# M8.net
KiCad netlist of a schematic drawn in Altium Designer
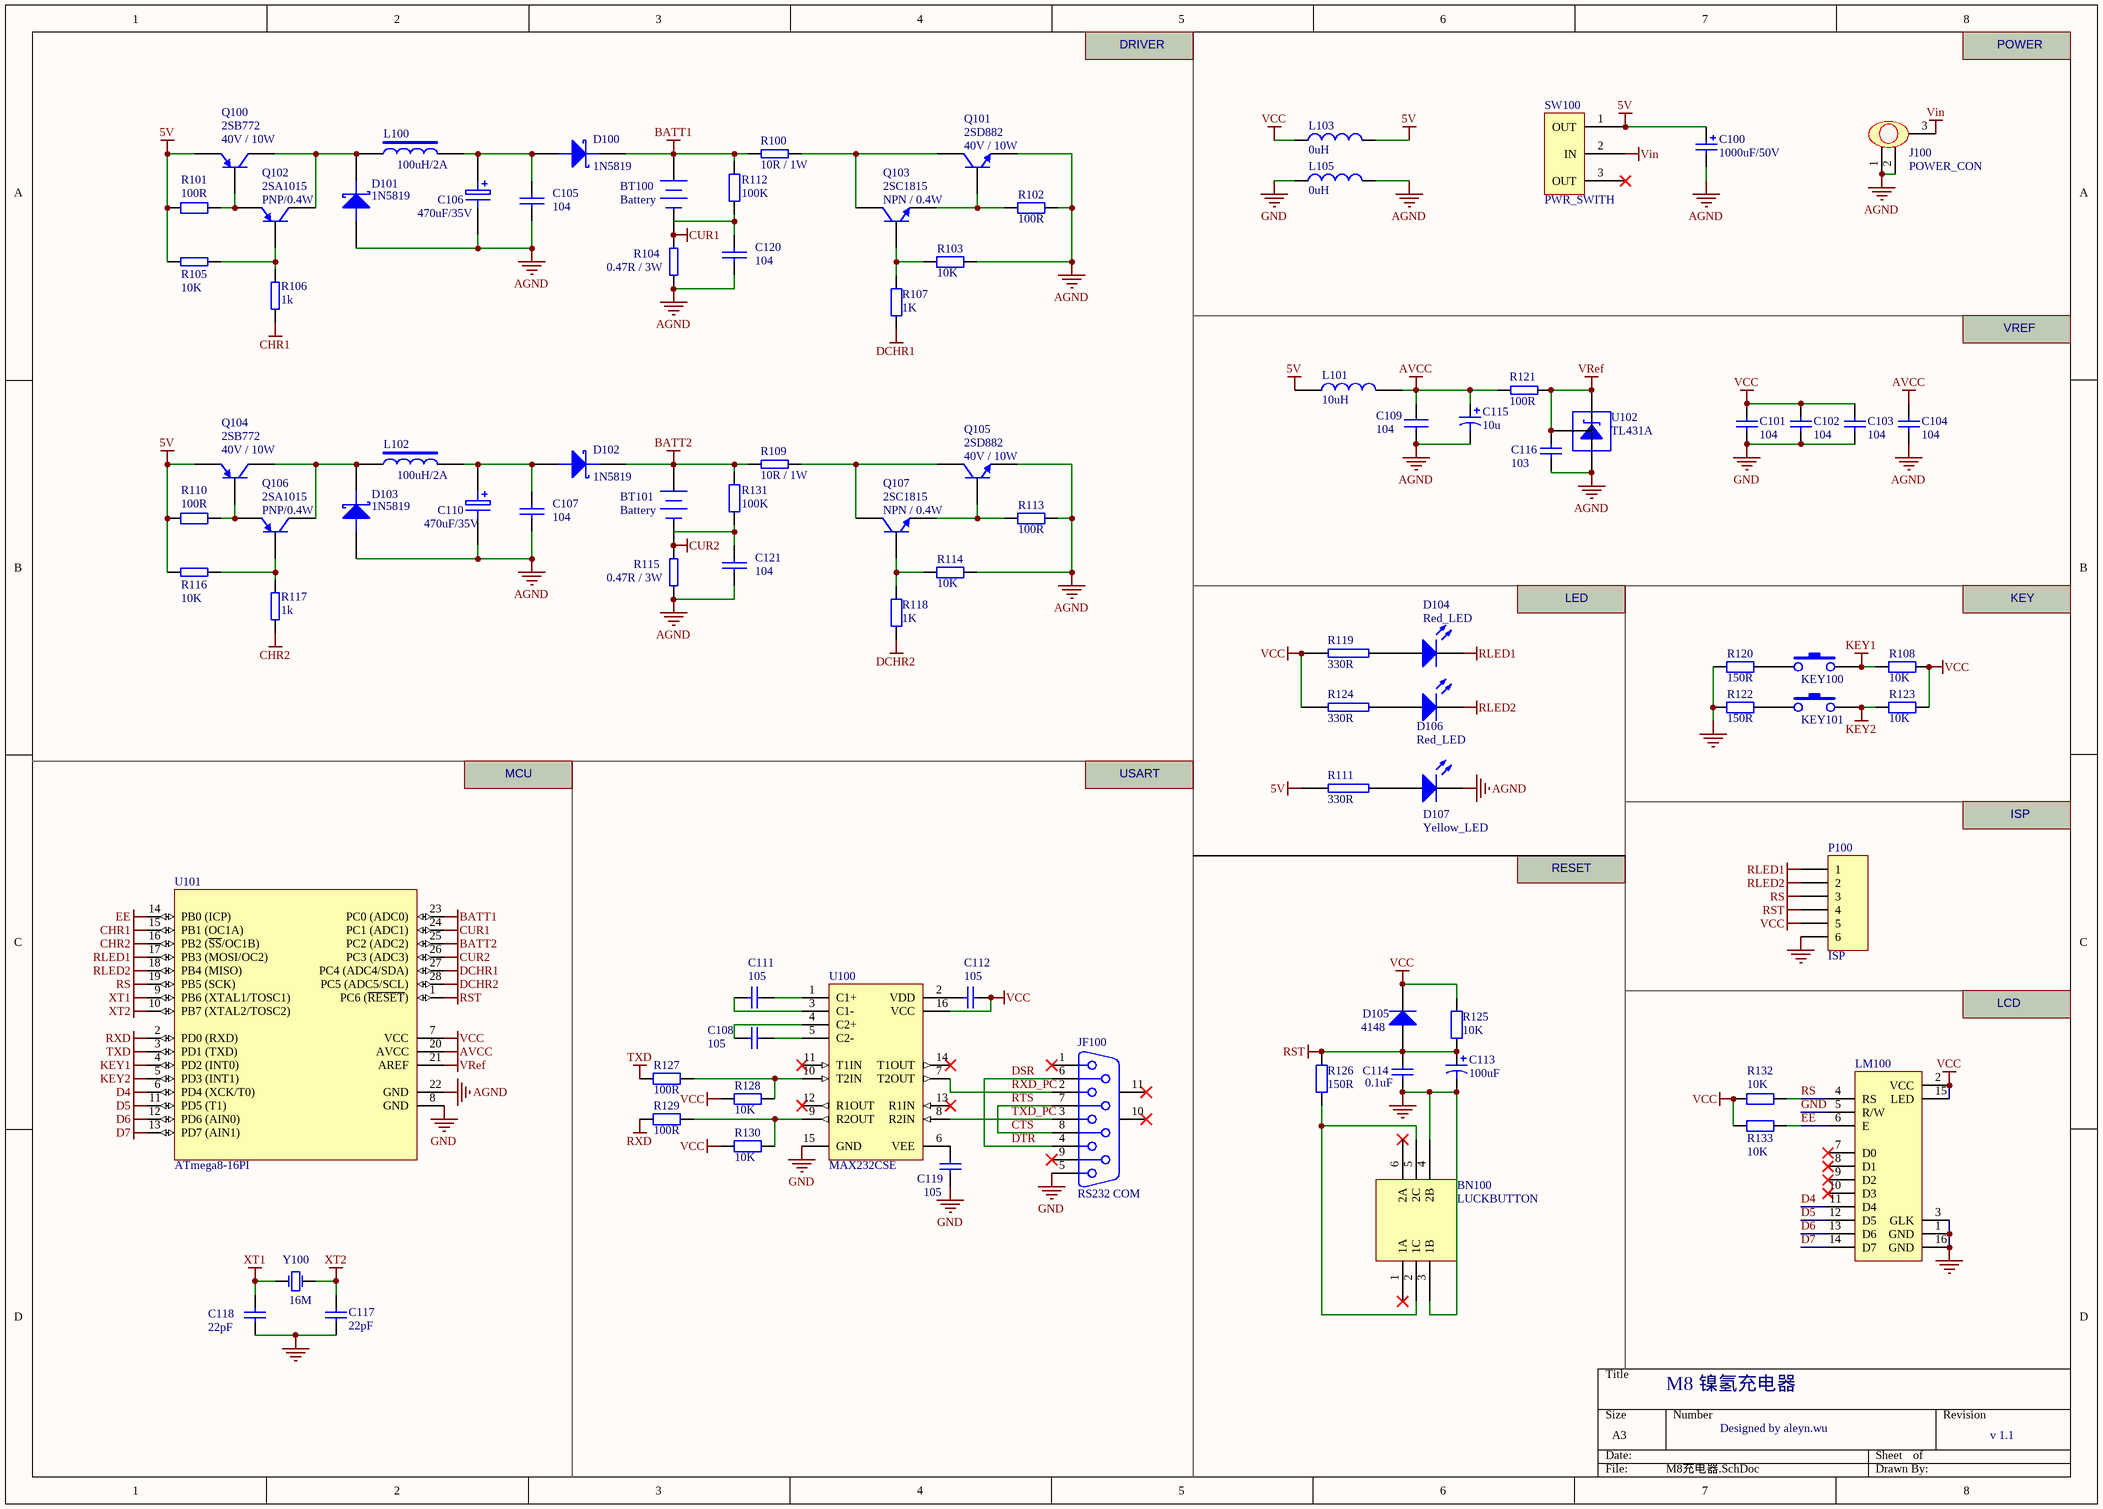
[diagram p0: M8充电器.SchDoc]

(export (version "E")
  (design (tool "Eeschema 10.0.6"))
  (components
    (comp (ref "BN100")
      (value "LUCKBUTTON")
      (footprint "LBTN-01")
      (libsource (lib "AVR_Library") (part "LUCKBUTTON"))
    )
    (comp (ref "BT100")
      (value "Battery")
      (footprint "BAT-2")
      (description "Multicell Battery")
      (fields (field (name "PUBLISHER") "Altium Limited"))
      (libsource (lib "Miscellaneous Devices") (part "Battery"))
    )
    (comp (ref "BT101")
      (value "Battery")
      (footprint "BAT-2")
      (description "Multicell Battery")
      (fields (field (name "PUBLISHER") "Altium Limited"))
      (libsource (lib "Miscellaneous Devices") (part "Battery"))
    )
    (comp (ref "C100")
      (value "1000uF/50V")
      (footprint "C1000uF/50V")
      (description "Polarized Capacitor (Radial)")
      (fields
        (field (name "MANUFACTURER") "Generic Components")
        (field (name "PUBLISHER") "Altium Hobart Technology Centre")
      )
      (libsource (lib "") (part "Cap Pol1_1"))
    )
    (comp (ref "C101")
      (value "104")
      (footprint "0805")
      (description "Capacitor")
      (fields (field (name "PUBLISHER") "Altium Limited"))
      (libsource (lib "Miscellaneous Devices") (part "Cap"))
    )
    (comp (ref "C102")
      (value "104")
      (footprint "0805")
      (description "Capacitor")
      (fields (field (name "PUBLISHER") "Altium Limited"))
      (libsource (lib "Miscellaneous Devices") (part "Cap"))
    )
    (comp (ref "C103")
      (value "104")
      (footprint "0805")
      (description "Capacitor")
      (fields (field (name "PUBLISHER") "Altium Limited"))
      (libsource (lib "Miscellaneous Devices") (part "Cap"))
    )
    (comp (ref "C104")
      (value "104")
      (footprint "0805")
      (description "Capacitor")
      (fields
        (field (name "MANUFACTURER") "Generic Components")
        (field (name "PUBLISHER") "Altium Hobart Technology Centre")
      )
      (libsource (lib "") (part "Cap_1"))
    )
    (comp (ref "C105")
      (value "104")
      (footprint "0805")
      (description "Capacitor")
      (libsource (lib "*") (part "CAP"))
    )
    (comp (ref "C106")
      (value "470uF/35V")
      (footprint "C1000uF/16V")
      (description "Electrolytic Capacitor")
      (libsource (lib "*") (part "ELECTRO1"))
    )
    (comp (ref "C107")
      (value "104")
      (footprint "0805")
      (description "Capacitor")
      (libsource (lib "*") (part "CAP"))
    )
    (comp (ref "C108")
      (value "105")
      (footprint "0805")
      (description "Capacitor")
      (fields
        (field (name "MANUFACTURER") "Generic Components")
        (field (name "PUBLISHER") "Altium Hobart Technology Centre")
      )
      (libsource (lib "Miscellaneous Devices") (part "Cap"))
    )
    (comp (ref "C109") (value "104") (footprint "0805") (libsource (lib "") (part "CAP_1")))
    (comp (ref "C110")
      (value "470uF/35V")
      (footprint "C1000uF/16V")
      (description "Electrolytic Capacitor")
      (libsource (lib "*") (part "ELECTRO1"))
    )
    (comp (ref "C111")
      (value "105")
      (footprint "0805")
      (description "Capacitor")
      (fields
        (field (name "MANUFACTURER") "Generic Components")
        (field (name "PUBLISHER") "Altium Hobart Technology Centre")
      )
      (libsource (lib "Miscellaneous Devices") (part "Cap"))
    )
    (comp (ref "C112")
      (value "105")
      (footprint "0805")
      (description "Capacitor")
      (fields
        (field (name "MANUFACTURER") "Generic Components")
        (field (name "PUBLISHER") "Altium Hobart Technology Centre")
      )
      (libsource (lib "") (part "Cap_1"))
    )
    (comp (ref "C113")
      (value "100uF")
      (footprint "1210")
      (description "Polarized Capacitor (Radial)")
      (fields (field (name "PUBLISHER") "Altium Limited"))
      (libsource (lib "Miscellaneous Devices") (part "Cap Pol1"))
    )
    (comp (ref "C114")
      (value "0.1uF")
      (footprint "0805")
      (description "Capacitor")
      (fields (field (name "PUBLISHER") "Altium Limited"))
      (libsource (lib "Miscellaneous Devices") (part "Cap"))
    )
    (comp (ref "C115")
      (value "10u")
      (footprint "C100UF/10V")
      (description "Polarized Capacitor (Radial)")
      (fields (field (name "PUBLISHER") "Altium Limited"))
      (libsource (lib "Miscellaneous Devices") (part "Cap Pol1"))
    )
    (comp (ref "C116")
      (value "103")
      (footprint "0805")
      (description "Capacitor")
      (fields (field (name "PUBLISHER") "Altium Limited"))
      (libsource (lib "Miscellaneous Devices") (part "Cap"))
    )
    (comp (ref "C117")
      (value "22pF")
      (footprint "0805")
      (description "Capacitor")
      (fields (field (name "PUBLISHER") "Altium Limited"))
      (libsource (lib "Miscellaneous Devices") (part "Cap"))
    )
    (comp (ref "C118")
      (value "22pF")
      (footprint "0805")
      (description "Capacitor")
      (fields (field (name "PUBLISHER") "Altium Limited"))
      (libsource (lib "Miscellaneous Devices") (part "Cap"))
    )
    (comp (ref "C119")
      (value "105")
      (footprint "0805")
      (description "Capacitor")
      (fields
        (field (name "MANUFACTURER") "Generic Components")
        (field (name "PUBLISHER") "Altium Hobart Technology Centre")
      )
      (libsource (lib "Miscellaneous Devices") (part "Cap"))
    )
    (comp (ref "C120")
      (value "104")
      (footprint "0805")
      (description "Capacitor")
      (libsource (lib "*") (part "CAP"))
    )
    (comp (ref "C121")
      (value "104")
      (footprint "0805")
      (description "Capacitor")
      (libsource (lib "*") (part "CAP"))
    )
    (comp (ref "D100")
      (value "1N5819")
      (footprint "IN5822")
      (description "Schottky Diode")
      (libsource (lib "*") (part "DIODE SCHOTTKY"))
    )
    (comp (ref "D101")
      (value "1N5819")
      (footprint "IN5822")
      (description "Schottky Diode")
      (libsource (lib "*") (part "DIODE SCHOTTKY"))
    )
    (comp (ref "D102")
      (value "1N5819")
      (footprint "IN5822")
      (description "Schottky Diode")
      (libsource (lib "*") (part "DIODE SCHOTTKY"))
    )
    (comp (ref "D103")
      (value "1N5819")
      (footprint "IN5822")
      (description "Schottky Diode")
      (libsource (lib "*") (part "DIODE SCHOTTKY"))
    )
    (comp (ref "D104")
      (value "Red_LED")
      (footprint "LED2")
      (description "Typical INFRARED GaAs LED")
      (fields (field (name "PUBLISHER") "Altium Limited"))
      (libsource (lib "Miscellaneous Devices") (part "LED0"))
    )
    (comp (ref "D105")
      (value "4148")
      (footprint "1206D")
      (description "1 Amp General Purpose Rectifier")
      (fields (field (name "PUBLISHER") "Altium Limited"))
      (libsource (lib "Miscellaneous Devices") (part "Diode 1N4001"))
    )
    (comp (ref "D106")
      (value "Red_LED")
      (footprint "LED2")
      (description "Typical INFRARED GaAs LED")
      (fields (field (name "PUBLISHER") "Altium Limited"))
      (libsource (lib "Miscellaneous Devices") (part "LED0"))
    )
    (comp (ref "D107")
      (value "Yellow_LED")
      (footprint "LED2")
      (description "Typical INFRARED GaAs LED")
      (fields (field (name "PUBLISHER") "Altium Limited"))
      (libsource (lib "Miscellaneous Devices") (part "LED0"))
    )
    (comp (ref "J100")
      (value "POWER_CON")
      (footprint "POWER_CON")
      (description "Power Connect")
      (libsource (lib "AVR_Library") (part "POWER_CON"))
    )
    (comp (ref "JF100")
      (value "RS232 COM")
      (footprint "DSUB1.385-2H9")
      (fields
        (field (name "MANUFACTURER") "Generic Components")
        (field (name "PUBLISHER") "Altium Hobart Technology Centre")
      )
      (libsource (lib "AVR_Library") (part "RS232 COM"))
    )
    (comp (ref "KEY100") (value "~") (footprint "BUTTON1") (libsource (lib "*") (part "SW-PB")))
    (comp (ref "KEY101") (value "~") (footprint "BUTTON1") (libsource (lib "*") (part "SW-PB")))
    (comp (ref "L100") (value "100uH/2A") (footprint "INDU20UH") (libsource (lib "*") (part "INDUCTOR2")))
    (comp (ref "L101") (value "10uH") (footprint "1206") (libsource (lib "*") (part "INDUCTOR")))
    (comp (ref "L102") (value "100uH/2A") (footprint "INDU20UH") (libsource (lib "*") (part "INDUCTOR2")))
    (comp (ref "L103")
      (value "0uH")
      (footprint "RES_V1W")
      (description "Inductor")
      (fields
        (field (name "MANUFACTURER") "Generic Components")
        (field (name "PUBLISHER") "Altium Hobart Technology Centre")
      )
      (libsource (lib "Miscellaneous Devices") (part "Inductor"))
    )
    (comp (ref "L105")
      (value "0uH")
      (footprint "RES_V1W")
      (description "Inductor")
      (fields
        (field (name "MANUFACTURER") "Generic Components")
        (field (name "PUBLISHER") "Altium Hobart Technology Centre")
      )
      (libsource (lib "Miscellaneous Devices") (part "Inductor"))
    )
    (comp (ref "LM100")
      (value "TC1602")
      (footprint "HDR2X7")
      (description "LCD TC1602B")
      (libsource (lib "AVR_Library") (part "TC1602B"))
    )
    (comp (ref "P100")
      (value "ISP")
      (footprint "HDR1X6")
      (description "Header, 6-Pin")
      (fields (field (name "PUBLISHER") "Altium Limited"))
      (libsource (lib "Miscellaneous Connectors") (part "Header 6"))
    )
    (comp (ref "Q100")
      (value "2SB772")
      (footprint "TO-262-AA")
      (description "PNP General Purpose Amplifier")
      (fields (field (name "PUBLISHER") "40V / 10W"))
      (libsource (lib "Miscellaneous Devices") (part "2N3906"))
    )
    (comp (ref "Q101")
      (value "2SD882")
      (footprint "TO-262-AA")
      (description "NPN General Purpose Amplifier")
      (fields (field (name "PUBLISHED") "40V / 10W") (field (name "PUBLISHER") "Altium Limited"))
      (libsource (lib "Miscellaneous Devices") (part "2N3904"))
    )
    (comp (ref "Q102")
      (value "2SA1015")
      (footprint "SOT-23/2")
      (description "PNP General Purpose Amplifier")
      (fields (field (name "PUBLISHED") "PNP/0.4W") (field (name "PUBLISHER") "Altium Limited"))
      (libsource (lib "Miscellaneous Devices") (part "2N3906"))
    )
    (comp (ref "Q103")
      (value "2SC1815")
      (footprint "SOT-23/2")
      (description "NPN General Purpose Amplifier")
      (fields (field (name "PUBLISHED") "NPN / 0.4W") (field (name "PUBLISHER") "Altium Limited"))
      (libsource (lib "Miscellaneous Devices") (part "2N3904"))
    )
    (comp (ref "Q104")
      (value "2SB772")
      (footprint "TO-262-AA")
      (description "PNP General Purpose Amplifier")
      (fields (field (name "PUBLISHER") "40V / 10W"))
      (libsource (lib "Miscellaneous Devices") (part "2N3906"))
    )
    (comp (ref "Q105")
      (value "2SD882")
      (footprint "TO-262-AA")
      (description "NPN General Purpose Amplifier")
      (fields (field (name "PUBLISHED") "40V / 10W") (field (name "PUBLISHER") "Altium Limited"))
      (libsource (lib "Miscellaneous Devices") (part "2N3904"))
    )
    (comp (ref "Q106")
      (value "2SA1015")
      (footprint "SOT-23/2")
      (description "PNP General Purpose Amplifier")
      (fields (field (name "PUBLISHED") "PNP/0.4W") (field (name "PUBLISHER") "Altium Limited"))
      (libsource (lib "Miscellaneous Devices") (part "2N3906"))
    )
    (comp (ref "Q107")
      (value "2SC1815")
      (footprint "SOT-23/2")
      (description "NPN General Purpose Amplifier")
      (fields (field (name "PUBLISHED") "NPN / 0.4W") (field (name "PUBLISHER") "Altium Limited"))
      (libsource (lib "Miscellaneous Devices") (part "2N3904"))
    )
    (comp (ref "R100") (value "10R / 1W") (footprint "AXIAL-0.6") (libsource (lib "*") (part "RES5")))
    (comp (ref "R101")
      (value "100R")
      (footprint "AXIAL-0.4")
      (description "Resistor")
      (fields (field (name "PUBLISHER") "Altium Limited"))
      (libsource (lib "") (part "Res2_2"))
    )
    (comp (ref "R102")
      (value "100R")
      (footprint "AXIAL-0.4")
      (description "Resistor")
      (fields (field (name "PUBLISHER") "Altium Limited"))
      (libsource (lib "Miscellaneous Devices") (part "Res2"))
    )
    (comp (ref "R103")
      (value "10K")
      (footprint "0805")
      (description "Resistor")
      (fields (field (name "PUBLISHER") "Altium Limited"))
      (libsource (lib "Miscellaneous Devices") (part "Res2"))
    )
    (comp (ref "R104") (value "0.47R / 3W") (footprint "AXIAL-0.7") (libsource (lib "*") (part "RES5")))
    (comp (ref "R105") (value "10K") (footprint "0805") (libsource (lib "*") (part "RES5")))
    (comp (ref "R106") (value "1k") (footprint "0805") (libsource (lib "*") (part "RES5")))
    (comp (ref "R107")
      (value "1K")
      (footprint "0805")
      (description "Resistor")
      (fields (field (name "PUBLISHER") "Altium Limited"))
      (libsource (lib "") (part "Res2_3"))
    )
    (comp (ref "R108")
      (value "10K")
      (footprint "0805")
      (description "Resistor")
      (fields (field (name "PUBLISHER") "Altium Limited"))
      (libsource (lib "Miscellaneous Devices") (part "Res2"))
    )
    (comp (ref "R109") (value "10R / 1W") (footprint "AXIAL-0.6") (libsource (lib "*") (part "RES5")))
    (comp (ref "R110")
      (value "100R")
      (footprint "AXIAL-0.4")
      (description "Resistor")
      (fields (field (name "PUBLISHER") "Altium Limited"))
      (libsource (lib "") (part "Res2_2"))
    )
    (comp (ref "R111") (value "330R") (footprint "0805") (libsource (lib "*") (part "RES2")))
    (comp (ref "R112")
      (value "100K")
      (footprint "0805")
      (description "Resistor")
      (fields (field (name "PUBLISHER") "Altium Limited"))
      (libsource (lib "") (part "Res2_1"))
    )
    (comp (ref "R113")
      (value "100R")
      (footprint "AXIAL-0.4")
      (description "Resistor")
      (fields (field (name "PUBLISHER") "Altium Limited"))
      (libsource (lib "Miscellaneous Devices") (part "Res2"))
    )
    (comp (ref "R114")
      (value "10K")
      (footprint "0805")
      (description "Resistor")
      (fields (field (name "PUBLISHER") "Altium Limited"))
      (libsource (lib "Miscellaneous Devices") (part "Res2"))
    )
    (comp (ref "R115") (value "0.47R / 3W") (footprint "AXIAL-0.7") (libsource (lib "*") (part "RES5")))
    (comp (ref "R116") (value "10K") (footprint "0805") (libsource (lib "*") (part "RES5")))
    (comp (ref "R117") (value "1k") (footprint "0805") (libsource (lib "*") (part "RES5")))
    (comp (ref "R118")
      (value "1K")
      (footprint "0805")
      (description "Resistor")
      (fields (field (name "PUBLISHER") "Altium Limited"))
      (libsource (lib "") (part "Res2_3"))
    )
    (comp (ref "R119") (value "330R") (footprint "0805") (libsource (lib "*") (part "RES2")))
    (comp (ref "R120")
      (value "150R")
      (footprint "0805")
      (description "Resistor")
      (fields (field (name "PUBLISHER") "Altium Limited"))
      (libsource (lib "Miscellaneous Devices") (part "Res2"))
    )
    (comp (ref "R121") (value "100R") (footprint "0805") (libsource (lib "*") (part "RES5")))
    (comp (ref "R122")
      (value "150R")
      (footprint "0805")
      (description "Resistor")
      (fields (field (name "PUBLISHER") "Altium Limited"))
      (libsource (lib "Miscellaneous Devices") (part "Res2"))
    )
    (comp (ref "R123")
      (value "10K")
      (footprint "0805")
      (description "Resistor")
      (fields (field (name "PUBLISHER") "Altium Limited"))
      (libsource (lib "Miscellaneous Devices") (part "Res2"))
    )
    (comp (ref "R124") (value "330R") (footprint "0805") (libsource (lib "*") (part "RES2")))
    (comp (ref "R125")
      (value "10K")
      (footprint "0805")
      (description "Resistor")
      (fields (field (name "PUBLISHER") "Altium Limited"))
      (libsource (lib "") (part "Res2_1"))
    )
    (comp (ref "R126")
      (value "150R")
      (footprint "0805")
      (description "Resistor")
      (fields (field (name "PUBLISHER") "Altium Limited"))
      (libsource (lib "") (part "Res2_3"))
    )
    (comp (ref "R127")
      (value "100R")
      (footprint "0805")
      (description "Resistor")
      (fields (field (name "PUBLISHER") "Altium Limited"))
      (libsource (lib "") (part "Res2_2"))
    )
    (comp (ref "R128")
      (value "10K")
      (footprint "0805")
      (description "Resistor")
      (fields (field (name "PUBLISHER") "Altium Limited"))
      (libsource (lib "") (part "Res2_3"))
    )
    (comp (ref "R129")
      (value "100R")
      (footprint "0805")
      (description "Resistor")
      (fields (field (name "PUBLISHER") "Altium Limited"))
      (libsource (lib "") (part "Res2_2"))
    )
    (comp (ref "R130")
      (value "10K")
      (footprint "0805")
      (description "Resistor")
      (fields (field (name "PUBLISHER") "Altium Limited"))
      (libsource (lib "") (part "Res2_1"))
    )
    (comp (ref "R131")
      (value "100K")
      (footprint "0805")
      (description "Resistor")
      (fields (field (name "PUBLISHER") "Altium Limited"))
      (libsource (lib "") (part "Res2_1"))
    )
    (comp (ref "R132")
      (value "10K")
      (footprint "0805")
      (description "Resistor")
      (fields (field (name "PUBLISHER") "Altium Limited"))
      (libsource (lib "") (part "Res2_2"))
    )
    (comp (ref "R133")
      (value "10K")
      (footprint "0805")
      (description "Resistor")
      (fields (field (name "PUBLISHER") "Altium Limited"))
      (libsource (lib "") (part "Res2_2"))
    )
    (comp (ref "SW100")
      (value "PWR_SWITH")
      (footprint "POWER_SWITCH2")
      (description "Power Switch")
      (libsource (lib "AVR_Library") (part "PWR_SWITH"))
    )
    (comp (ref "U100")
      (value "MAX232CSE")
      (footprint "SO-16")
      (description "+5V Powered RS-232 Driver/Receiver")
      (fields
        (field (name "MANUFACTURER") "Maxim")
        (field (name "PUBLISHER") "Altium Hobart Technology Centre")
      )
      (libsource (lib "Maxim Communication Transceiver") (part "MAX232CPE"))
    )
    (comp (ref "U101")
      (value "ATmega8-16PI")
      (footprint "32A_N")
      (description "8-Bit AVR Microcontroller with 8K Bytes of In-System Programmable Flash Memory")
      (fields (field (name "PUBLISHER") "Altium Limited"))
      (libsource (lib "Atmel Microcontroller 8-Bit AVR") (part "ATmega8-16PI"))
    )
    (comp (ref "U102") (value "TL431A") (footprint "SOT-89") (libsource (lib "AVR_Library") (part "TL431")))
    (comp (ref "Y100")
      (value "16M")
      (footprint "XTAL")
      (description "Crystal Oscillator")
      (fields
        (field (name "MANUFACTURER") "Generic Components")
        (field (name "PUBLISHER") "Altium Hobart Technology Centre")
      )
      (libsource (lib "AVR_Library") (part "XTAL"))
    )
  )
  (nets
    (net (code "1") (name "/CTS") (class "Default")
      (node (ref "JF100") (pin "7") (pinfunction "7_7") (pintype "passive"))
      (node (ref "JF100") (pin "8") (pinfunction "8_8") (pintype "passive"))
    )
    (net (code "2") (name "/DSR") (class "Default")
      (node (ref "JF100") (pin "4") (pinfunction "4_4") (pintype "passive"))
      (node (ref "JF100") (pin "6") (pinfunction "6_6") (pintype "passive"))
    )
    (net (code "3") (name "/RXD_PC") (class "Default")
      (node (ref "JF100") (pin "2") (pinfunction "2_2") (pintype "passive"))
      (node (ref "U100") (pin "7") (pinfunction "T2OUT_7") (pintype "output"))
    )
    (net (code "4") (name "/TXD_PC") (class "Default")
      (node (ref "JF100") (pin "3") (pinfunction "3_3") (pintype "passive"))
      (node (ref "U100") (pin "8") (pinfunction "R2IN_8") (pintype "input"))
    )
    (net (code "5") (name "5V") (class "Default")
      (node (ref "C100") (pin "1") (pinfunction "1_1") (pintype "passive"))
      (node (ref "L101") (pin "1") (pinfunction "1_1") (pintype "passive"))
      (node (ref "L103") (pin "1") (pinfunction "1_1") (pintype "passive"))
      (node (ref "Q100") (pin "1") (pinfunction "E_1") (pintype "passive"))
      (node (ref "Q104") (pin "1") (pinfunction "E_1") (pintype "passive"))
      (node (ref "R101") (pin "1") (pinfunction "1_1") (pintype "passive"))
      (node (ref "R105") (pin "1") (pinfunction "1_1") (pintype "passive"))
      (node (ref "R110") (pin "1") (pinfunction "1_1") (pintype "passive"))
      (node (ref "R111") (pin "2") (pinfunction "2_2") (pintype "passive"))
      (node (ref "R116") (pin "1") (pinfunction "1_1") (pintype "passive"))
      (node (ref "SW100") (pin "1") (pinfunction "OUT_1") (pintype "passive"))
    )
    (net (code "6") (name "AGND") (class "Default")
      (node (ref "C100") (pin "2") (pinfunction "2_2") (pintype "passive"))
      (node (ref "C104") (pin "2") (pinfunction "2_2") (pintype "passive"))
      (node (ref "C105") (pin "2") (pinfunction "2_2") (pintype "passive"))
      (node (ref "C106") (pin "2") (pinfunction "2_2") (pintype "passive"))
      (node (ref "C107") (pin "2") (pinfunction "2_2") (pintype "passive"))
      (node (ref "C109") (pin "2") (pinfunction "2_2") (pintype "passive"))
      (node (ref "C110") (pin "2") (pinfunction "2_2") (pintype "passive"))
      (node (ref "C115") (pin "2") (pinfunction "2_2") (pintype "passive"))
      (node (ref "C116") (pin "1") (pinfunction "1_1") (pintype "passive"))
      (node (ref "C120") (pin "2") (pinfunction "2_2") (pintype "passive"))
      (node (ref "C121") (pin "2") (pinfunction "2_2") (pintype "passive"))
      (node (ref "D101") (pin "1") (pinfunction "A_1") (pintype "passive"))
      (node (ref "D103") (pin "1") (pinfunction "A_1") (pintype "passive"))
      (node (ref "D107") (pin "2") (pinfunction "K_2") (pintype "passive"))
      (node (ref "J100") (pin "1") (pintype "power_in"))
      (node (ref "J100") (pin "2") (pintype "power_in"))
      (node (ref "L105") (pin "1") (pinfunction "1_1") (pintype "passive"))
      (node (ref "Q101") (pin "1") (pinfunction "E_1") (pintype "passive"))
      (node (ref "Q105") (pin "1") (pinfunction "E_1") (pintype "passive"))
      (node (ref "R102") (pin "1") (pinfunction "1_1") (pintype "passive"))
      (node (ref "R103") (pin "1") (pinfunction "1_1") (pintype "passive"))
      (node (ref "R104") (pin "1") (pinfunction "1_1") (pintype "passive"))
      (node (ref "R113") (pin "1") (pinfunction "1_1") (pintype "passive"))
      (node (ref "R114") (pin "1") (pinfunction "1_1") (pintype "passive"))
      (node (ref "R115") (pin "1") (pinfunction "1_1") (pintype "passive"))
      (node (ref "U101") (pin "22") (pinfunction "GND_22") (pintype "power_in"))
      (node (ref "U102") (pin "2") (pinfunction "2_2") (pintype "power_in"))
    )
    (net (code "7") (name "AVCC") (class "Default")
      (node (ref "C104") (pin "1") (pinfunction "1_1") (pintype "passive"))
      (node (ref "C109") (pin "1") (pinfunction "1_1") (pintype "passive"))
      (node (ref "C115") (pin "1") (pinfunction "1_1") (pintype "passive"))
      (node (ref "L101") (pin "2") (pinfunction "2_2") (pintype "passive"))
      (node (ref "R121") (pin "1") (pinfunction "1_1") (pintype "passive"))
      (node (ref "U101") (pin "20") (pinfunction "AVCC_20") (pintype "power_in"))
    )
    (net (code "8") (name "BATT1") (class "Default")
      (node (ref "BT100") (pin "1") (pinfunction "+_1") (pintype "passive"))
      (node (ref "D100") (pin "2") (pinfunction "K_2") (pintype "passive"))
      (node (ref "R100") (pin "2") (pinfunction "2_2") (pintype "passive"))
      (node (ref "R112") (pin "1") (pinfunction "1_1") (pintype "passive"))
      (node (ref "U101") (pin "23") (pinfunction "PC0_(ADC0)_23") (pintype "bidirectional"))
    )
    (net (code "9") (name "BATT2") (class "Default")
      (node (ref "BT101") (pin "1") (pinfunction "+_1") (pintype "passive"))
      (node (ref "D102") (pin "2") (pinfunction "K_2") (pintype "passive"))
      (node (ref "R109") (pin "2") (pinfunction "2_2") (pintype "passive"))
      (node (ref "R131") (pin "1") (pinfunction "1_1") (pintype "passive"))
      (node (ref "U101") (pin "25") (pinfunction "PC2_(ADC2)_25") (pintype "bidirectional"))
    )
    (net (code "10") (name "CHR1") (class "Default")
      (node (ref "R106") (pin "2") (pinfunction "2_2") (pintype "passive"))
      (node (ref "U101") (pin "15") (pinfunction "PB1_(OC1A)_15") (pintype "bidirectional"))
    )
    (net (code "11") (name "CHR2") (class "Default")
      (node (ref "R117") (pin "2") (pinfunction "2_2") (pintype "passive"))
      (node (ref "U101") (pin "16") (pinfunction "PB2_(~{SS}/OC1B)_16") (pintype "bidirectional"))
    )
    (net (code "12") (name "CUR1") (class "Default")
      (node (ref "BT100") (pin "2") (pinfunction "-_2") (pintype "passive"))
      (node (ref "R104") (pin "2") (pinfunction "2_2") (pintype "passive"))
      (node (ref "U101") (pin "24") (pinfunction "PC1_(ADC1)_24") (pintype "bidirectional"))
    )
    (net (code "13") (name "CUR2") (class "Default")
      (node (ref "BT101") (pin "2") (pinfunction "-_2") (pintype "passive"))
      (node (ref "R115") (pin "2") (pinfunction "2_2") (pintype "passive"))
      (node (ref "U101") (pin "26") (pinfunction "PC3_(ADC3)_26") (pintype "bidirectional"))
    )
    (net (code "14") (name "D4") (class "Default")
      (node (ref "LM100") (pin "11") (pinfunction "D4_11") (pintype "passive"))
      (node (ref "U101") (pin "6") (pinfunction "PD4_(XCK/T0)_6") (pintype "bidirectional"))
    )
    (net (code "15") (name "D5") (class "Default")
      (node (ref "LM100") (pin "12") (pinfunction "D5_12") (pintype "passive"))
      (node (ref "U101") (pin "11") (pinfunction "PD5_(T1)_11") (pintype "bidirectional"))
    )
    (net (code "16") (name "D6") (class "Default")
      (node (ref "LM100") (pin "13") (pinfunction "D6_13") (pintype "passive"))
      (node (ref "U101") (pin "12") (pinfunction "PD6_(AIN0)_12") (pintype "bidirectional"))
    )
    (net (code "17") (name "D7") (class "Default")
      (node (ref "LM100") (pin "14") (pinfunction "D7_14") (pintype "passive"))
      (node (ref "U101") (pin "13") (pinfunction "PD7_(AIN1)_13") (pintype "bidirectional"))
    )
    (net (code "18") (name "DCHR1") (class "Default")
      (node (ref "R107") (pin "1") (pinfunction "1_1") (pintype "passive"))
      (node (ref "U101") (pin "27") (pinfunction "PC4_(ADC4/SDA)_27") (pintype "bidirectional"))
    )
    (net (code "19") (name "DCHR2") (class "Default")
      (node (ref "R118") (pin "1") (pinfunction "1_1") (pintype "passive"))
      (node (ref "U101") (pin "28") (pinfunction "PC5_(ADC5/SCL)_28") (pintype "bidirectional"))
    )
    (net (code "20") (name "EE") (class "Default")
      (node (ref "LM100") (pin "6") (pinfunction "E_6") (pintype "passive"))
      (node (ref "R133") (pin "2") (pinfunction "2_2") (pintype "passive"))
      (node (ref "U101") (pin "14") (pinfunction "PB0_(ICP)_14") (pintype "bidirectional"))
    )
    (net (code "21") (name "GND") (class "Default")
      (node (ref "BN100") (pin "3") (pinfunction "1B_3") (pintype "passive"))
      (node (ref "BN100") (pin "4") (pinfunction "2B_4") (pintype "passive"))
      (node (ref "C101") (pin "1") (pinfunction "1_1") (pintype "passive"))
      (node (ref "C102") (pin "1") (pinfunction "1_1") (pintype "passive"))
      (node (ref "C103") (pin "2") (pinfunction "2_2") (pintype "passive"))
      (node (ref "C113") (pin "2") (pinfunction "2_2") (pintype "passive"))
      (node (ref "C114") (pin "2") (pinfunction "2_2") (pintype "passive"))
      (node (ref "C117") (pin "2") (pinfunction "2_2") (pintype "passive"))
      (node (ref "C118") (pin "2") (pinfunction "2_2") (pintype "passive"))
      (node (ref "C119") (pin "1") (pinfunction "1_1") (pintype "passive"))
      (node (ref "JF100") (pin "5") (pinfunction "5_5") (pintype "passive"))
      (node (ref "L105") (pin "2") (pinfunction "2_2") (pintype "passive"))
      (node (ref "LM100") (pin "1") (pinfunction "GND_1") (pintype "passive"))
      (node (ref "LM100") (pin "16") (pinfunction "GND_16") (pintype "passive"))
      (node (ref "LM100") (pin "3") (pinfunction "GLK_3") (pintype "passive"))
      (node (ref "LM100") (pin "5") (pinfunction "R/W_5") (pintype "passive"))
      (node (ref "P100") (pin "6") (pinfunction "6_6") (pintype "passive"))
      (node (ref "R120") (pin "2") (pinfunction "2_2") (pintype "passive"))
      (node (ref "R122") (pin "2") (pinfunction "2_2") (pintype "passive"))
      (node (ref "U100") (pin "15") (pinfunction "GND_15") (pintype "power_in"))
      (node (ref "U101") (pin "8") (pinfunction "GND_8") (pintype "power_in"))
    )
    (net (code "22") (name "KEY1") (class "Default")
      (node (ref "KEY100") (pin "2") (pinfunction "2_2") (pintype "passive"))
      (node (ref "R108") (pin "2") (pinfunction "2_2") (pintype "passive"))
      (node (ref "U101") (pin "4") (pinfunction "PD2_(INT0)_4") (pintype "bidirectional"))
    )
    (net (code "23") (name "KEY2") (class "Default")
      (node (ref "KEY101") (pin "2") (pinfunction "2_2") (pintype "passive"))
      (node (ref "R123") (pin "2") (pinfunction "2_2") (pintype "passive"))
      (node (ref "U101") (pin "5") (pinfunction "PD3_(INT1)_5") (pintype "bidirectional"))
    )
    (net (code "24") (name "Net-(BN100-1C)") (class "Default")
      (node (ref "BN100") (pin "2") (pinfunction "1C_2") (pintype "passive"))
      (node (ref "BN100") (pin "5") (pinfunction "2C_5") (pintype "passive"))
      (node (ref "R126") (pin "1") (pinfunction "1_1") (pintype "passive"))
    )
    (net (code "25") (name "Net-(C120-Pad1)") (class "Default")
      (node (ref "C120") (pin "1") (pinfunction "1_1") (pintype "passive"))
      (node (ref "R112") (pin "2") (pinfunction "2_2") (pintype "passive"))
    )
    (net (code "26") (name "Net-(C121-Pad1)") (class "Default")
      (node (ref "C121") (pin "1") (pinfunction "1_1") (pintype "passive"))
      (node (ref "R131") (pin "2") (pinfunction "2_2") (pintype "passive"))
    )
    (net (code "27") (name "Net-(D100-A)") (class "Default")
      (node (ref "C105") (pin "1") (pinfunction "1_1") (pintype "passive"))
      (node (ref "C106") (pin "1") (pinfunction "1_1") (pintype "passive"))
      (node (ref "D100") (pin "1") (pinfunction "A_1") (pintype "passive"))
      (node (ref "L100") (pin "2") (pinfunction "2_2") (pintype "passive"))
    )
    (net (code "28") (name "Net-(D101-K)") (class "Default")
      (node (ref "D101") (pin "2") (pinfunction "K_2") (pintype "passive"))
      (node (ref "L100") (pin "1") (pinfunction "1_1") (pintype "passive"))
      (node (ref "Q100") (pin "3") (pinfunction "C_3") (pintype "passive"))
      (node (ref "Q102") (pin "3") (pinfunction "C_3") (pintype "passive"))
    )
    (net (code "29") (name "Net-(D102-A)") (class "Default")
      (node (ref "C107") (pin "1") (pinfunction "1_1") (pintype "passive"))
      (node (ref "C110") (pin "1") (pinfunction "1_1") (pintype "passive"))
      (node (ref "D102") (pin "1") (pinfunction "A_1") (pintype "passive"))
      (node (ref "L102") (pin "2") (pinfunction "2_2") (pintype "passive"))
    )
    (net (code "30") (name "Net-(D103-K)") (class "Default")
      (node (ref "D103") (pin "2") (pinfunction "K_2") (pintype "passive"))
      (node (ref "L102") (pin "1") (pinfunction "1_1") (pintype "passive"))
      (node (ref "Q104") (pin "3") (pinfunction "C_3") (pintype "passive"))
      (node (ref "Q106") (pin "3") (pinfunction "C_3") (pintype "passive"))
    )
    (net (code "31") (name "Net-(D104-A)") (class "Default")
      (node (ref "D104") (pin "1") (pinfunction "A_1") (pintype "passive"))
      (node (ref "R119") (pin "1") (pinfunction "1_1") (pintype "passive"))
    )
    (net (code "32") (name "Net-(D106-A)") (class "Default")
      (node (ref "D106") (pin "1") (pinfunction "A_1") (pintype "passive"))
      (node (ref "R124") (pin "1") (pinfunction "1_1") (pintype "passive"))
    )
    (net (code "33") (name "Net-(D107-A)") (class "Default")
      (node (ref "D107") (pin "1") (pinfunction "A_1") (pintype "passive"))
      (node (ref "R111") (pin "1") (pinfunction "1_1") (pintype "passive"))
    )
    (net (code "34") (name "Net-(KEY100-Pad1)") (class "Default")
      (node (ref "KEY100") (pin "1") (pinfunction "1_1") (pintype "passive"))
      (node (ref "R120") (pin "1") (pinfunction "1_1") (pintype "passive"))
    )
    (net (code "35") (name "Net-(KEY101-Pad1)") (class "Default")
      (node (ref "KEY101") (pin "1") (pinfunction "1_1") (pintype "passive"))
      (node (ref "R122") (pin "1") (pinfunction "1_1") (pintype "passive"))
    )
    (net (code "36") (name "Net-(Q100-B)") (class "Default")
      (node (ref "Q100") (pin "2") (pinfunction "B_2") (pintype "passive"))
      (node (ref "Q102") (pin "1") (pinfunction "E_1") (pintype "passive"))
      (node (ref "R101") (pin "2") (pinfunction "2_2") (pintype "passive"))
    )
    (net (code "37") (name "Net-(Q101-B)") (class "Default")
      (node (ref "Q101") (pin "2") (pinfunction "B_2") (pintype "passive"))
      (node (ref "Q103") (pin "1") (pinfunction "E_1") (pintype "passive"))
      (node (ref "R102") (pin "2") (pinfunction "2_2") (pintype "passive"))
    )
    (net (code "38") (name "Net-(Q101-C)") (class "Default")
      (node (ref "Q101") (pin "3") (pinfunction "C_3") (pintype "passive"))
      (node (ref "Q103") (pin "3") (pinfunction "C_3") (pintype "passive"))
      (node (ref "R100") (pin "1") (pinfunction "1_1") (pintype "passive"))
    )
    (net (code "39") (name "Net-(Q102-B)") (class "Default")
      (node (ref "Q102") (pin "2") (pinfunction "B_2") (pintype "passive"))
      (node (ref "R105") (pin "2") (pinfunction "2_2") (pintype "passive"))
      (node (ref "R106") (pin "1") (pinfunction "1_1") (pintype "passive"))
    )
    (net (code "40") (name "Net-(Q103-B)") (class "Default")
      (node (ref "Q103") (pin "2") (pinfunction "B_2") (pintype "passive"))
      (node (ref "R103") (pin "2") (pinfunction "2_2") (pintype "passive"))
      (node (ref "R107") (pin "2") (pinfunction "2_2") (pintype "passive"))
    )
    (net (code "41") (name "Net-(Q104-B)") (class "Default")
      (node (ref "Q104") (pin "2") (pinfunction "B_2") (pintype "passive"))
      (node (ref "Q106") (pin "1") (pinfunction "E_1") (pintype "passive"))
      (node (ref "R110") (pin "2") (pinfunction "2_2") (pintype "passive"))
    )
    (net (code "42") (name "Net-(Q105-B)") (class "Default")
      (node (ref "Q105") (pin "2") (pinfunction "B_2") (pintype "passive"))
      (node (ref "Q107") (pin "1") (pinfunction "E_1") (pintype "passive"))
      (node (ref "R113") (pin "2") (pinfunction "2_2") (pintype "passive"))
    )
    (net (code "43") (name "Net-(Q105-C)") (class "Default")
      (node (ref "Q105") (pin "3") (pinfunction "C_3") (pintype "passive"))
      (node (ref "Q107") (pin "3") (pinfunction "C_3") (pintype "passive"))
      (node (ref "R109") (pin "1") (pinfunction "1_1") (pintype "passive"))
    )
    (net (code "44") (name "Net-(Q106-B)") (class "Default")
      (node (ref "Q106") (pin "2") (pinfunction "B_2") (pintype "passive"))
      (node (ref "R116") (pin "2") (pinfunction "2_2") (pintype "passive"))
      (node (ref "R117") (pin "1") (pinfunction "1_1") (pintype "passive"))
    )
    (net (code "45") (name "Net-(Q107-B)") (class "Default")
      (node (ref "Q107") (pin "2") (pinfunction "B_2") (pintype "passive"))
      (node (ref "R114") (pin "2") (pinfunction "2_2") (pintype "passive"))
      (node (ref "R118") (pin "2") (pinfunction "2_2") (pintype "passive"))
    )
    (net (code "46") (name "Net-(U100-C1+)") (class "Default")
      (node (ref "C111") (pin "2") (pinfunction "2_2") (pintype "passive"))
      (node (ref "U100") (pin "1") (pinfunction "C1+_1") (pintype "passive"))
    )
    (net (code "47") (name "Net-(U100-C1-)") (class "Default")
      (node (ref "C111") (pin "1") (pinfunction "1_1") (pintype "passive"))
      (node (ref "U100") (pin "3") (pinfunction "C1-_3") (pintype "passive"))
    )
    (net (code "48") (name "Net-(U100-C2+)") (class "Default")
      (node (ref "C108") (pin "1") (pinfunction "1_1") (pintype "passive"))
      (node (ref "U100") (pin "4") (pinfunction "C2+_4") (pintype "passive"))
    )
    (net (code "49") (name "Net-(U100-C2-)") (class "Default")
      (node (ref "C108") (pin "2") (pinfunction "2_2") (pintype "passive"))
      (node (ref "U100") (pin "5") (pinfunction "C2-_5") (pintype "passive"))
    )
    (net (code "50") (name "Net-(U100-R2OUT)") (class "Default")
      (node (ref "R129") (pin "2") (pinfunction "2_2") (pintype "passive"))
      (node (ref "R130") (pin "1") (pinfunction "1_1") (pintype "passive"))
      (node (ref "U100") (pin "9") (pinfunction "R2OUT_9") (pintype "output"))
    )
    (net (code "51") (name "Net-(U100-T2IN)") (class "Default")
      (node (ref "R127") (pin "2") (pinfunction "2_2") (pintype "passive"))
      (node (ref "R128") (pin "2") (pinfunction "2_2") (pintype "passive"))
      (node (ref "U100") (pin "10") (pinfunction "T2IN_10") (pintype "input"))
    )
    (net (code "52") (name "Net-(U100-VDD)") (class "Default")
      (node (ref "C112") (pin "1") (pinfunction "1_1") (pintype "passive"))
      (node (ref "U100") (pin "2") (pinfunction "VDD_2") (pintype "power_in"))
    )
    (net (code "53") (name "Net-(U100-VEE)") (class "Default")
      (node (ref "C119") (pin "2") (pinfunction "2_2") (pintype "passive"))
      (node (ref "U100") (pin "6") (pinfunction "VEE_6") (pintype "power_in"))
    )
    (net (code "54") (name "RLED1") (class "Default")
      (node (ref "D104") (pin "2") (pinfunction "K_2") (pintype "passive"))
      (node (ref "P100") (pin "1") (pinfunction "1_1") (pintype "passive"))
      (node (ref "U101") (pin "17") (pinfunction "PB3_(MOSI/OC2)_17") (pintype "bidirectional"))
    )
    (net (code "55") (name "RLED2") (class "Default")
      (node (ref "D106") (pin "2") (pinfunction "K_2") (pintype "passive"))
      (node (ref "P100") (pin "2") (pinfunction "2_2") (pintype "passive"))
      (node (ref "U101") (pin "18") (pinfunction "PB4_(MISO)_18") (pintype "bidirectional"))
    )
    (net (code "56") (name "RS") (class "Default")
      (node (ref "LM100") (pin "4") (pinfunction "RS_4") (pintype "passive"))
      (node (ref "P100") (pin "3") (pinfunction "3_3") (pintype "passive"))
      (node (ref "R132") (pin "2") (pinfunction "2_2") (pintype "passive"))
      (node (ref "U101") (pin "19") (pinfunction "PB5_(SCK)_19") (pintype "bidirectional"))
    )
    (net (code "57") (name "RST") (class "Default")
      (node (ref "C113") (pin "1") (pinfunction "1_1") (pintype "passive"))
      (node (ref "C114") (pin "1") (pinfunction "1_1") (pintype "passive"))
      (node (ref "D105") (pin "1") (pinfunction "A_1") (pintype "passive"))
      (node (ref "P100") (pin "4") (pinfunction "4_4") (pintype "passive"))
      (node (ref "R125") (pin "2") (pinfunction "2_2") (pintype "passive"))
      (node (ref "R126") (pin "2") (pinfunction "2_2") (pintype "passive"))
      (node (ref "U101") (pin "1") (pinfunction "PC6_(~{RESET})_1") (pintype "bidirectional"))
    )
    (net (code "58") (name "RXD") (class "Default")
      (node (ref "R129") (pin "1") (pinfunction "1_1") (pintype "passive"))
      (node (ref "U101") (pin "2") (pinfunction "PD0_(RXD)_2") (pintype "bidirectional"))
    )
    (net (code "59") (name "TXD") (class "Default")
      (node (ref "R127") (pin "1") (pinfunction "1_1") (pintype "passive"))
      (node (ref "U101") (pin "3") (pinfunction "PD1_(TXD)_3") (pintype "bidirectional"))
    )
    (net (code "60") (name "VCC") (class "Default")
      (node (ref "C101") (pin "2") (pinfunction "2_2") (pintype "passive"))
      (node (ref "C102") (pin "2") (pinfunction "2_2") (pintype "passive"))
      (node (ref "C103") (pin "1") (pinfunction "1_1") (pintype "passive"))
      (node (ref "C112") (pin "2") (pinfunction "2_2") (pintype "passive"))
      (node (ref "D105") (pin "2") (pinfunction "K_2") (pintype "passive"))
      (node (ref "L103") (pin "2") (pinfunction "2_2") (pintype "passive"))
      (node (ref "LM100") (pin "15") (pinfunction "LED_15") (pintype "passive"))
      (node (ref "LM100") (pin "2") (pinfunction "VCC_2") (pintype "passive"))
      (node (ref "P100") (pin "5") (pinfunction "5_5") (pintype "passive"))
      (node (ref "R108") (pin "1") (pinfunction "1_1") (pintype "passive"))
      (node (ref "R119") (pin "2") (pinfunction "2_2") (pintype "passive"))
      (node (ref "R123") (pin "1") (pinfunction "1_1") (pintype "passive"))
      (node (ref "R124") (pin "2") (pinfunction "2_2") (pintype "passive"))
      (node (ref "R125") (pin "1") (pinfunction "1_1") (pintype "passive"))
      (node (ref "R128") (pin "1") (pinfunction "1_1") (pintype "passive"))
      (node (ref "R130") (pin "2") (pinfunction "2_2") (pintype "passive"))
      (node (ref "R132") (pin "1") (pinfunction "1_1") (pintype "passive"))
      (node (ref "R133") (pin "1") (pinfunction "1_1") (pintype "passive"))
      (node (ref "U100") (pin "16") (pinfunction "VCC_16") (pintype "power_in"))
      (node (ref "U101") (pin "7") (pinfunction "VCC_7") (pintype "power_in"))
    )
    (net (code "61") (name "VRef") (class "Default")
      (node (ref "C116") (pin "2") (pinfunction "2_2") (pintype "passive"))
      (node (ref "R121") (pin "2") (pinfunction "2_2") (pintype "passive"))
      (node (ref "U101") (pin "21") (pinfunction "AREF_21") (pintype "passive"))
      (node (ref "U102") (pin "1") (pinfunction "1_1") (pintype "power_in"))
      (node (ref "U102") (pin "3") (pinfunction "3_3") (pintype "power_in"))
    )
    (net (code "62") (name "Vin") (class "Default")
      (node (ref "J100") (pin "3") (pintype "power_in"))
      (node (ref "SW100") (pin "2") (pinfunction "IN_2") (pintype "passive"))
    )
    (net (code "63") (name "XT1") (class "Default")
      (node (ref "C118") (pin "1") (pinfunction "1_1") (pintype "passive"))
      (node (ref "U101") (pin "9") (pinfunction "PB6_(XTAL1/TOSC1)_9") (pintype "bidirectional"))
      (node (ref "Y100") (pin "1") (pinfunction "OSC1_1") (pintype "passive"))
    )
    (net (code "64") (name "XT2") (class "Default")
      (node (ref "C117") (pin "1") (pinfunction "1_1") (pintype "passive"))
      (node (ref "U101") (pin "10") (pinfunction "PB7_(XTAL2/TOSC2)_10") (pintype "bidirectional"))
      (node (ref "Y100") (pin "2") (pinfunction "OSC2_2") (pintype "passive"))
    )
    (net (code "65") (name "unconnected-(BN100-1A-Pad1)") (class "Default")
      (node (ref "BN100") (pin "1") (pinfunction "1A_1") (pintype "passive+no_connect"))
    )
    (net (code "66") (name "unconnected-(BN100-2A-Pad6)") (class "Default")
      (node (ref "BN100") (pin "6") (pinfunction "2A_6") (pintype "passive+no_connect"))
    )
    (net (code "67") (name "unconnected-(JF100-MH1-Pad10)") (class "Default")
      (node (ref "JF100") (pin "10") (pinfunction "MH1_10") (pintype "passive+no_connect"))
    )
    (net (code "68") (name "unconnected-(JF100-MH2-Pad11)") (class "Default")
      (node (ref "JF100") (pin "11") (pinfunction "MH2_11") (pintype "passive+no_connect"))
    )
    (net (code "69") (name "unconnected-(JF100-Pad1)") (class "Default")
      (node (ref "JF100") (pin "1") (pinfunction "1_1") (pintype "passive+no_connect"))
    )
    (net (code "70") (name "unconnected-(JF100-Pad9)") (class "Default")
      (node (ref "JF100") (pin "9") (pinfunction "9_9") (pintype "passive+no_connect"))
    )
    (net (code "71") (name "unconnected-(LM100-D0-Pad7)") (class "Default")
      (node (ref "LM100") (pin "7") (pinfunction "D0_7") (pintype "passive+no_connect"))
    )
    (net (code "72") (name "unconnected-(LM100-D1-Pad8)") (class "Default")
      (node (ref "LM100") (pin "8") (pinfunction "D1_8") (pintype "passive+no_connect"))
    )
    (net (code "73") (name "unconnected-(LM100-D2-Pad9)") (class "Default")
      (node (ref "LM100") (pin "9") (pinfunction "D2_9") (pintype "passive+no_connect"))
    )
    (net (code "74") (name "unconnected-(LM100-D3-Pad10)") (class "Default")
      (node (ref "LM100") (pin "10") (pinfunction "D3_10") (pintype "passive+no_connect"))
    )
    (net (code "75") (name "unconnected-(SW100-OUT-Pad3)") (class "Default")
      (node (ref "SW100") (pin "3") (pinfunction "OUT_3") (pintype "passive+no_connect"))
    )
    (net (code "76") (name "unconnected-(U100-R1IN-Pad13)") (class "Default")
      (node (ref "U100") (pin "13") (pinfunction "R1IN_13") (pintype "input+no_connect"))
    )
    (net (code "77") (name "unconnected-(U100-R1OUT-Pad12)") (class "Default")
      (node (ref "U100") (pin "12") (pinfunction "R1OUT_12") (pintype "output+no_connect"))
    )
    (net (code "78") (name "unconnected-(U100-T1IN-Pad11)") (class "Default")
      (node (ref "U100") (pin "11") (pinfunction "T1IN_11") (pintype "input+no_connect"))
    )
    (net (code "79") (name "unconnected-(U100-T1OUT-Pad14)") (class "Default")
      (node (ref "U100") (pin "14") (pinfunction "T1OUT_14") (pintype "output+no_connect"))
    )
  )
)
